# PaxInstrument-T400.net
KiCad netlist of a schematic drawn in EAGLE
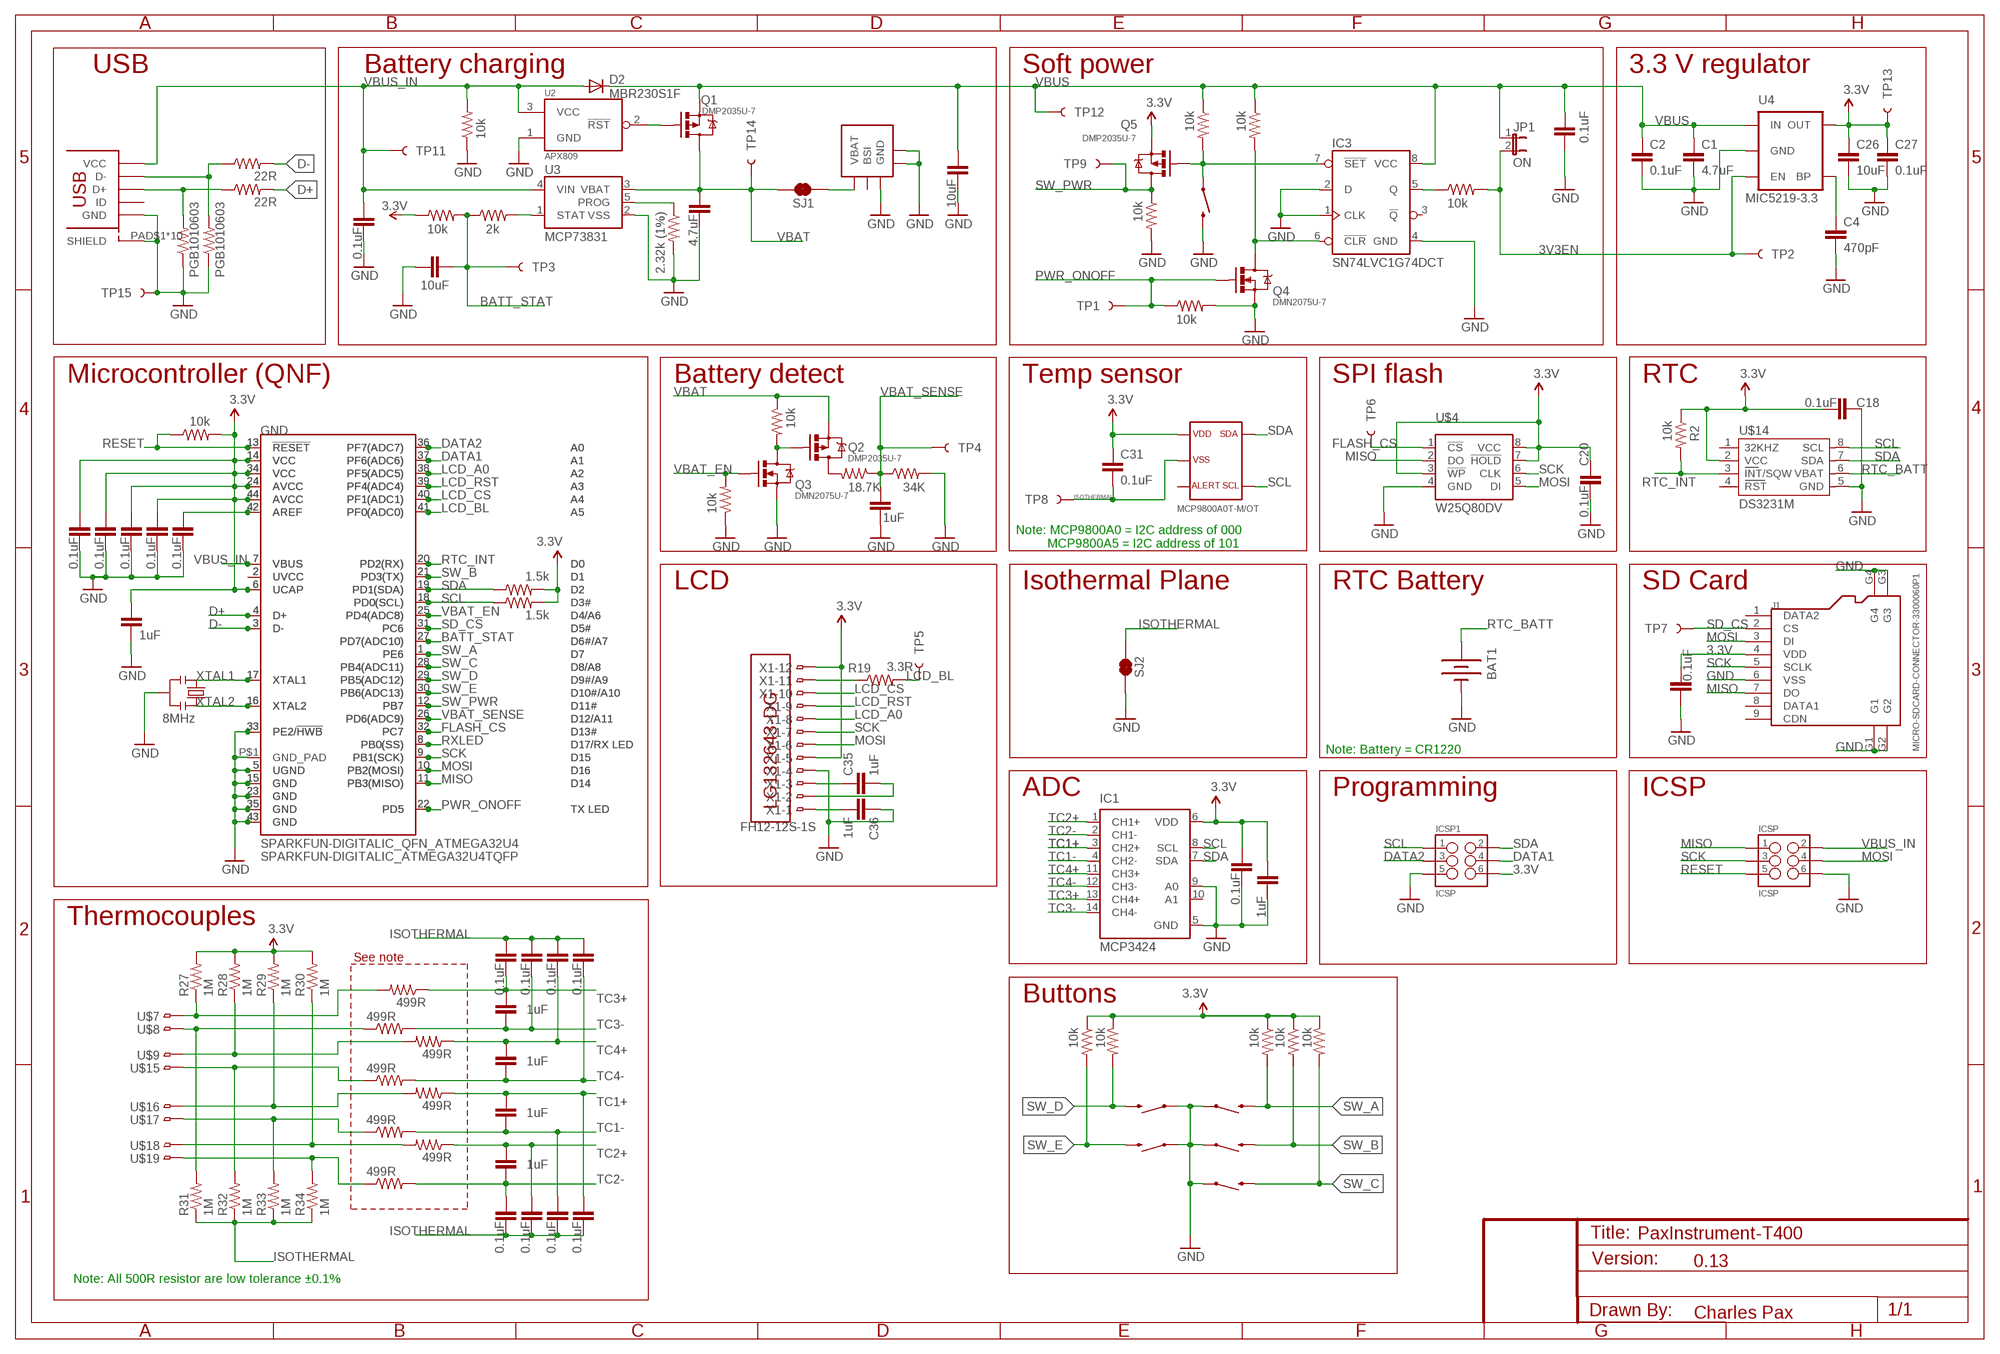
[diagram p0: schematic, sheet 1]

(export (version "E")
  (design (tool "Eeschema 10.0.6"))
  (components
    (comp (ref "BAT1")
      (value "BATTERY12MM")
      (footprint "eagle-import:BATTCON_12MM")
      (fields (field (name "MF") "Keystone Electronics") (field (name "MPN") "3000TR"))
      (libsource (lib "eagle-import") (part "BATTERY12MM"))
    )
    (comp (ref "C1")
      (value "4.7uF")
      (footprint "eagle-import:SPARKFUN-CAPACITORS_0603-CAP")
      (libsource (lib "eagle-import") (part "SPARKFUN-CAPACITORS_CAP0603-CAP"))
    )
    (comp (ref "C2")
      (value "0.1uF")
      (footprint "eagle-import:SPARKFUN-CAPACITORS_0603-CAP")
      (libsource (lib "eagle-import") (part "SPARKFUN-CAPACITORS_CAP0603-CAP"))
    )
    (comp (ref "C3")
      (value "0.1uF")
      (footprint "eagle-import:SPARKFUN-CAPACITORS_0603-CAP")
      (libsource (lib "eagle-import") (part "SPARKFUN-CAPACITORS_CAP0603-CAP"))
    )
    (comp (ref "C4")
      (value "470pF")
      (footprint "eagle-import:SPARKFUN-CAPACITORS_0603-CAP")
      (libsource (lib "eagle-import") (part "SPARKFUN-CAPACITORS_CAP0603-CAP"))
    )
    (comp (ref "C5")
      (value "0.1uF")
      (footprint "eagle-import:SPARKFUN-CAPACITORS_0603-CAP")
      (libsource (lib "eagle-import") (part "SPARKFUN-CAPACITORS_CAP0603-CAP"))
    )
    (comp (ref "C6")
      (value "0.1uF")
      (footprint "eagle-import:SPARKFUN-CAPACITORS_0603-CAP")
      (libsource (lib "eagle-import") (part "SPARKFUN-CAPACITORS_CAP0603-CAP"))
    )
    (comp (ref "C7")
      (value "1uF")
      (footprint "eagle-import:SPARKFUN-CAPACITORS_0603-CAP")
      (libsource (lib "eagle-import") (part "SPARKFUN-CAPACITORS_CAP0603-CAP"))
    )
    (comp (ref "C8")
      (value "1uF")
      (footprint "eagle-import:SPARKFUN-CAPACITORS_0603-CAP")
      (libsource (lib "eagle-import") (part "SPARKFUN-CAPACITORS_CAP0603-CAP"))
    )
    (comp (ref "C9")
      (value "4.7uF")
      (footprint "eagle-import:SPARKFUN-CAPACITORS_0603-CAP")
      (libsource (lib "eagle-import") (part "SPARKFUN-CAPACITORS_CAP0603-CAP"))
    )
    (comp (ref "C10")
      (value "1uF")
      (footprint "eagle-import:SPARKFUN-CAPACITORS_0603-CAP")
      (libsource (lib "eagle-import") (part "SPARKFUN-CAPACITORS_CAP0603-CAP"))
    )
    (comp (ref "C11")
      (value "1uF")
      (footprint "eagle-import:SPARKFUN-CAPACITORS_0603-CAP")
      (libsource (lib "eagle-import") (part "SPARKFUN-CAPACITORS_CAP0603-CAP"))
    )
    (comp (ref "C12")
      (value "10uF")
      (footprint "eagle-import:SPARKFUN-CAPACITORS_0603-CAP")
      (libsource (lib "eagle-import") (part "SPARKFUN-CAPACITORS_CAP0603-CAP"))
    )
    (comp (ref "C13")
      (value "0.1uF")
      (footprint "eagle-import:SPARKFUN-CAPACITORS_0603-CAP")
      (libsource (lib "eagle-import") (part "SPARKFUN-CAPACITORS_CAP0603-CAP"))
    )
    (comp (ref "C14")
      (value "0.1uF")
      (footprint "eagle-import:SPARKFUN-CAPACITORS_0603-CAP")
      (libsource (lib "eagle-import") (part "SPARKFUN-CAPACITORS_CAP0603-CAP"))
    )
    (comp (ref "C15")
      (value "0.1uF")
      (footprint "eagle-import:SPARKFUN-CAPACITORS_0603-CAP")
      (libsource (lib "eagle-import") (part "SPARKFUN-CAPACITORS_CAP0603-CAP"))
    )
    (comp (ref "C16")
      (value "0.1uF")
      (footprint "eagle-import:SPARKFUN-CAPACITORS_0603-CAP")
      (libsource (lib "eagle-import") (part "SPARKFUN-CAPACITORS_CAP0603-CAP"))
    )
    (comp (ref "C17")
      (value "0.1uF")
      (footprint "eagle-import:SPARKFUN-CAPACITORS_0603-CAP")
      (libsource (lib "eagle-import") (part "SPARKFUN-CAPACITORS_CAP0603-CAP"))
    )
    (comp (ref "C18")
      (value "0.1uF")
      (footprint "eagle-import:SPARKFUN-CAPACITORS_0603-CAP")
      (libsource (lib "eagle-import") (part "SPARKFUN-CAPACITORS_CAP0603-CAP"))
    )
    (comp (ref "C19")
      (value "1uF")
      (footprint "eagle-import:SPARKFUN-CAPACITORS_0603-CAP")
      (libsource (lib "eagle-import") (part "SPARKFUN-CAPACITORS_CAP0603-CAP"))
    )
    (comp (ref "C20")
      (value "0.1uF")
      (footprint "eagle-import:SPARKFUN-CAPACITORS_0603-CAP")
      (libsource (lib "eagle-import") (part "SPARKFUN-CAPACITORS_CAP0603-CAP"))
    )
    (comp (ref "C21")
      (value "0.1uF")
      (footprint "eagle-import:SPARKFUN-CAPACITORS_0603-CAP")
      (libsource (lib "eagle-import") (part "SPARKFUN-CAPACITORS_CAP0603-CAP"))
    )
    (comp (ref "C22")
      (value "10uF")
      (footprint "eagle-import:SPARKFUN-CAPACITORS_0603-CAP")
      (libsource (lib "eagle-import") (part "SPARKFUN-CAPACITORS_CAP0603-CAP"))
    )
    (comp (ref "C23")
      (value "1uF")
      (footprint "eagle-import:SPARKFUN-CAPACITORS_0603-CAP")
      (libsource (lib "eagle-import") (part "SPARKFUN-CAPACITORS_CAP0603-CAP"))
    )
    (comp (ref "C24")
      (value "0.1uF")
      (footprint "eagle-import:SPARKFUN-CAPACITORS_0603-CAP")
      (libsource (lib "eagle-import") (part "SPARKFUN-CAPACITORS_CAP0603-CAP"))
    )
    (comp (ref "C25")
      (value "0.1uF")
      (footprint "eagle-import:SPARKFUN-CAPACITORS_0603-CAP")
      (libsource (lib "eagle-import") (part "SPARKFUN-CAPACITORS_CAP0603-CAP"))
    )
    (comp (ref "C26")
      (value "10uF")
      (footprint "eagle-import:SPARKFUN-CAPACITORS_0603-CAP")
      (libsource (lib "eagle-import") (part "SPARKFUN-CAPACITORS_CAP0603-CAP"))
    )
    (comp (ref "C27")
      (value "0.1uF")
      (footprint "eagle-import:SPARKFUN-CAPACITORS_0603-CAP")
      (libsource (lib "eagle-import") (part "SPARKFUN-CAPACITORS_CAP0603-CAP"))
    )
    (comp (ref "C28")
      (value "0.1uF")
      (footprint "eagle-import:SPARKFUN-CAPACITORS_0603-CAP")
      (libsource (lib "eagle-import") (part "SPARKFUN-CAPACITORS_CAP0603-CAP"))
    )
    (comp (ref "C29")
      (value "0.1uF")
      (footprint "eagle-import:SPARKFUN-CAPACITORS_0603-CAP")
      (libsource (lib "eagle-import") (part "SPARKFUN-CAPACITORS_CAP0603-CAP"))
    )
    (comp (ref "C30")
      (value "1uF")
      (footprint "eagle-import:SPARKFUN-CAPACITORS_0603-CAP")
      (libsource (lib "eagle-import") (part "SPARKFUN-CAPACITORS_CAP0603-CAP"))
    )
    (comp (ref "C31")
      (value "0.1uF")
      (footprint "eagle-import:SPARKFUN-CAPACITORS_0603-CAP")
      (libsource (lib "eagle-import") (part "SPARKFUN-CAPACITORS_CAP0603-CAP"))
    )
    (comp (ref "C32")
      (value "0.1uF")
      (footprint "eagle-import:SPARKFUN-CAPACITORS_0603-CAP")
      (libsource (lib "eagle-import") (part "SPARKFUN-CAPACITORS_CAP0603-CAP"))
    )
    (comp (ref "C33")
      (value "0.1uF")
      (footprint "eagle-import:SPARKFUN-CAPACITORS_0603-CAP")
      (libsource (lib "eagle-import") (part "SPARKFUN-CAPACITORS_CAP0603-CAP"))
    )
    (comp (ref "C34")
      (value "0.1uF")
      (footprint "eagle-import:SPARKFUN-CAPACITORS_0603-CAP")
      (libsource (lib "eagle-import") (part "SPARKFUN-CAPACITORS_CAP0603-CAP"))
    )
    (comp (ref "C35")
      (value "1uF")
      (footprint "eagle-import:SPARKFUN-CAPACITORS_0603-CAP")
      (libsource (lib "eagle-import") (part "SPARKFUN-CAPACITORS_CAP0603-CAP"))
    )
    (comp (ref "C36")
      (value "1uF")
      (footprint "eagle-import:SPARKFUN-CAPACITORS_0603-CAP")
      (libsource (lib "eagle-import") (part "SPARKFUN-CAPACITORS_CAP0603-CAP"))
    )
    (comp (ref "C37")
      (value "0.1uF")
      (footprint "eagle-import:SPARKFUN-CAPACITORS_0603-CAP")
      (libsource (lib "eagle-import") (part "SPARKFUN-CAPACITORS_CAP0603-CAP"))
    )
    (comp (ref "D2")
      (value "MBR230S1F")
      (footprint "eagle-import:SOD123")
      (fields (field (name "MF") "DIODES INC") (field (name "MPN") "MBR230S1F-7"))
      (libsource (lib "eagle-import") (part "SPARKFUN-DISCRETESEMI_DIODESOD123SOD123"))
    )
    (comp (ref "GND")
      (value "SPARKFUN-DIGITALIC_QFN_ATMEGA32U4")
      (footprint "eagle-import:SPARKFUN-DIGITALIC_SPARKFUN-DIGITALIC_QFN-44")
      (fields (field (name "MF") "Atmel") (field (name "MPN") "ATMEGA32U4-MU"))
      (libsource (lib "eagle-import") (part "SPARKFUN-DIGITALIC_QFN_ATMEGA32U4"))
    )
    (comp (ref "IC1")
      (value "MCP3424")
      (footprint "eagle-import:SO14")
      (fields (field (name "MF") "Microchip Technology") (field (name "MPN") "MCP3424-E/SL"))
      (libsource (lib "eagle-import") (part "MCP3424"))
    )
    (comp (ref "IC3")
      (value "SN74LVC1G74DCT")
      (footprint "eagle-import:SSOP8")
      (fields (field (name "MF") "Texas Instruments") (field (name "MPN") "SN74LVC1G74DCTR "))
      (libsource (lib "eagle-import") (part "SN74LVC1G74DCT"))
    )
    (comp (ref "ICSP")
      (value "ICSP")
      (footprint "eagle-import:SPARKFUN-CONNECTORS_2X3_SMT_POSTS_PAXINSTRUMENT")
      (fields (field (name "MF") "FCI") (field (name "MPN") "95278-101A06LF"))
      (libsource (lib "eagle-import") (part "SPARKFUN-CONNECTORS_M03X2PAX"))
    )
    (comp (ref "ICSP1")
      (value "ICSP")
      (footprint "eagle-import:SPARKFUN-CONNECTORS_2X3_SMT_POSTS_PAXINSTRUMENT")
      (fields (field (name "MF") "FCI") (field (name "MPN") "95278-101A06LF"))
      (libsource (lib "eagle-import") (part "SPARKFUN-CONNECTORS_M03X2PAX"))
    )
    (comp (ref "J1")
      (value "MICRO-SDCARD-CONNECTOR-3300060P1")
      (footprint "eagle-import:9P-SMD-W-RING")
      (fields (field (name "MF") "SUNTECH") (field (name "MPN") "ST-TF-003A"))
      (libsource (lib "eagle-import") (part "MICRO-SDCARD-CONNECTOR-3300060P1"))
    )
    (comp (ref "JP1")
      (value "ON")
      (footprint "eagle-import:SJ_2S-NO")
      (libsource (lib "eagle-import") (part "JUMPER-2SMD-NO"))
    )
    (comp (ref "Q1")
      (value "DMP2035U-7")
      (footprint "eagle-import:SOT23")
      (fields (field (name "MF") "DIODES INC"))
      (libsource (lib "eagle-import") (part "MOSFET-PCHANNELSMT"))
    )
    (comp (ref "Q2")
      (value "DMP2035U-7")
      (footprint "eagle-import:SOT23")
      (fields (field (name "MF") "DIODES INC"))
      (libsource (lib "eagle-import") (part "MOSFET-PCHANNELSMT"))
    )
    (comp (ref "Q3")
      (value "DMN2075U-7")
      (footprint "eagle-import:SOT23")
      (fields (field (name "MF") "DIODES INC") (field (name "MPN") "DMN2075U-7 "))
      (libsource (lib "eagle-import") (part "MOSFET-NCHANNELSMT"))
    )
    (comp (ref "Q4")
      (value "DMN2075U-7")
      (footprint "eagle-import:SOT23")
      (fields (field (name "MF") "DIODES INC") (field (name "MPN") "DMN2075U-7 "))
      (libsource (lib "eagle-import") (part "MOSFET-NCHANNELSMT"))
    )
    (comp (ref "Q5")
      (value "DMP2035U-7")
      (footprint "eagle-import:SOT23")
      (fields (field (name "MF") "DIODES INC"))
      (libsource (lib "eagle-import") (part "MOSFET-PCHANNELSMT"))
    )
    (comp (ref "R1")
      (value "10k")
      (footprint "eagle-import:SPARKFUN-RESISTORS_0603-RES")
      (libsource (lib "eagle-import") (part "SPARKFUN-RESISTORS_RESISTOR0603-RES"))
    )
    (comp (ref "R2")
      (value "10k")
      (footprint "eagle-import:SPARKFUN-RESISTORS_0603-RES")
      (libsource (lib "eagle-import") (part "SPARKFUN-RESISTORS_RESISTOR0603-RES"))
    )
    (comp (ref "R3")
      (value "2.32k (1%)")
      (footprint "eagle-import:SPARKFUN-RESISTORS_0603-RES")
      (libsource (lib "eagle-import") (part "SPARKFUN-RESISTORS_RESISTOR0603-RES"))
    )
    (comp (ref "R4")
      (value "10k")
      (footprint "eagle-import:SPARKFUN-RESISTORS_0603-RES")
      (libsource (lib "eagle-import") (part "SPARKFUN-RESISTORS_RESISTOR0603-RES"))
    )
    (comp (ref "R5")
      (value "10k")
      (footprint "eagle-import:SPARKFUN-RESISTORS_0603-RES")
      (libsource (lib "eagle-import") (part "SPARKFUN-RESISTORS_RESISTOR0603-RES"))
    )
    (comp (ref "R6")
      (value "10k")
      (footprint "eagle-import:SPARKFUN-RESISTORS_0603-RES")
      (libsource (lib "eagle-import") (part "SPARKFUN-RESISTORS_RESISTOR0603-RES"))
    )
    (comp (ref "R7")
      (value "10k")
      (footprint "eagle-import:SPARKFUN-RESISTORS_0603-RES")
      (libsource (lib "eagle-import") (part "SPARKFUN-RESISTORS_RESISTOR0603-RES"))
    )
    (comp (ref "R8")
      (value "10k")
      (footprint "eagle-import:SPARKFUN-RESISTORS_0603-RES")
      (libsource (lib "eagle-import") (part "SPARKFUN-RESISTORS_RESISTOR0603-RES"))
    )
    (comp (ref "R9")
      (value "22R")
      (footprint "eagle-import:SPARKFUN-RESISTORS_0603-RES")
      (libsource (lib "eagle-import") (part "SPARKFUN-RESISTORS_RESISTOR0603-RES"))
    )
    (comp (ref "R10")
      (value "22R")
      (footprint "eagle-import:SPARKFUN-RESISTORS_0603-RES")
      (libsource (lib "eagle-import") (part "SPARKFUN-RESISTORS_RESISTOR0603-RES"))
    )
    (comp (ref "R11")
      (value "10k")
      (footprint "eagle-import:SPARKFUN-RESISTORS_0603-RES")
      (libsource (lib "eagle-import") (part "SPARKFUN-RESISTORS_RESISTOR0603-RES"))
    )
    (comp (ref "R12")
      (value "10k")
      (footprint "eagle-import:SPARKFUN-RESISTORS_0603-RES")
      (libsource (lib "eagle-import") (part "SPARKFUN-RESISTORS_RESISTOR0603-RES"))
    )
    (comp (ref "R13")
      (value "1.5k")
      (footprint "eagle-import:SPARKFUN-RESISTORS_0603-RES")
      (libsource (lib "eagle-import") (part "SPARKFUN-RESISTORS_RESISTOR0603-RES"))
    )
    (comp (ref "R14")
      (value "1.5k")
      (footprint "eagle-import:SPARKFUN-RESISTORS_0603-RES")
      (libsource (lib "eagle-import") (part "SPARKFUN-RESISTORS_RESISTOR0603-RES"))
    )
    (comp (ref "R15")
      (value "10k")
      (footprint "eagle-import:SPARKFUN-RESISTORS_0603-RES")
      (libsource (lib "eagle-import") (part "SPARKFUN-RESISTORS_RESISTOR0603-RES"))
    )
    (comp (ref "R16")
      (value "10k")
      (footprint "eagle-import:SPARKFUN-RESISTORS_0603-RES")
      (libsource (lib "eagle-import") (part "SPARKFUN-RESISTORS_RESISTOR0603-RES"))
    )
    (comp (ref "R17")
      (value "2k")
      (footprint "eagle-import:SPARKFUN-RESISTORS_0603-RES")
      (libsource (lib "eagle-import") (part "SPARKFUN-RESISTORS_RESISTOR0603-RES"))
    )
    (comp (ref "R18")
      (value "10k")
      (footprint "eagle-import:SPARKFUN-RESISTORS_0603-RES")
      (libsource (lib "eagle-import") (part "SPARKFUN-RESISTORS_RESISTOR0603-RES"))
    )
    (comp (ref "R19")
      (value "3.3R")
      (footprint "eagle-import:SPARKFUN-RESISTORS_0603-RES")
      (libsource (lib "eagle-import") (part "SPARKFUN-RESISTORS_RESISTOR0603-RES"))
    )
    (comp (ref "R20")
      (value "18.7K")
      (footprint "eagle-import:SPARKFUN-RESISTORS_0603-RES")
      (libsource (lib "eagle-import") (part "SPARKFUN-RESISTORS_RESISTOR0603-RES"))
    )
    (comp (ref "R21")
      (value "10k")
      (footprint "eagle-import:SPARKFUN-RESISTORS_0603-RES")
      (libsource (lib "eagle-import") (part "SPARKFUN-RESISTORS_RESISTOR0603-RES"))
    )
    (comp (ref "R22")
      (value "10k")
      (footprint "eagle-import:SPARKFUN-RESISTORS_0603-RES")
      (libsource (lib "eagle-import") (part "SPARKFUN-RESISTORS_RESISTOR0603-RES"))
    )
    (comp (ref "R23")
      (value "10k")
      (footprint "eagle-import:SPARKFUN-RESISTORS_0603-RES")
      (libsource (lib "eagle-import") (part "SPARKFUN-RESISTORS_RESISTOR0603-RES"))
    )
    (comp (ref "R24")
      (value "34K")
      (footprint "eagle-import:SPARKFUN-RESISTORS_0603-RES")
      (libsource (lib "eagle-import") (part "SPARKFUN-RESISTORS_RESISTOR0603-RES"))
    )
    (comp (ref "R25")
      (value "10k")
      (footprint "eagle-import:SPARKFUN-RESISTORS_0603-RES")
      (libsource (lib "eagle-import") (part "SPARKFUN-RESISTORS_RESISTOR0603-RES"))
    )
    (comp (ref "R27")
      (value "1M")
      (footprint "eagle-import:SPARKFUN-RESISTORS_0603-RES")
      (libsource (lib "eagle-import") (part "SPARKFUN-RESISTORS_RESISTOR0603-RES"))
    )
    (comp (ref "R28")
      (value "1M")
      (footprint "eagle-import:SPARKFUN-RESISTORS_0603-RES")
      (libsource (lib "eagle-import") (part "SPARKFUN-RESISTORS_RESISTOR0603-RES"))
    )
    (comp (ref "R29")
      (value "1M")
      (footprint "eagle-import:SPARKFUN-RESISTORS_0603-RES")
      (libsource (lib "eagle-import") (part "SPARKFUN-RESISTORS_RESISTOR0603-RES"))
    )
    (comp (ref "R30")
      (value "1M")
      (footprint "eagle-import:SPARKFUN-RESISTORS_0603-RES")
      (libsource (lib "eagle-import") (part "SPARKFUN-RESISTORS_RESISTOR0603-RES"))
    )
    (comp (ref "R31")
      (value "1M")
      (footprint "eagle-import:SPARKFUN-RESISTORS_0603-RES")
      (libsource (lib "eagle-import") (part "SPARKFUN-RESISTORS_RESISTOR0603-RES"))
    )
    (comp (ref "R32")
      (value "1M")
      (footprint "eagle-import:SPARKFUN-RESISTORS_0603-RES")
      (libsource (lib "eagle-import") (part "SPARKFUN-RESISTORS_RESISTOR0603-RES"))
    )
    (comp (ref "R33")
      (value "1M")
      (footprint "eagle-import:SPARKFUN-RESISTORS_0603-RES")
      (libsource (lib "eagle-import") (part "SPARKFUN-RESISTORS_RESISTOR0603-RES"))
    )
    (comp (ref "R34")
      (value "1M")
      (footprint "eagle-import:SPARKFUN-RESISTORS_0603-RES")
      (libsource (lib "eagle-import") (part "SPARKFUN-RESISTORS_RESISTOR0603-RES"))
    )
    (comp (ref "R35")
      (value "499R")
      (footprint "eagle-import:SPARKFUN-RESISTORS_0603-RES")
      (fields (field (name "MF") "Vishay") (field (name "MPN") "TNPW0603499RBEEA"))
      (libsource (lib "eagle-import") (part "SPARKFUN-RESISTORS_RESISTOR0603-RES"))
    )
    (comp (ref "R36")
      (value "499R")
      (footprint "eagle-import:SPARKFUN-RESISTORS_0603-RES")
      (fields (field (name "MF") "Vishay") (field (name "MPN") "TNPW0603499RBEEA"))
      (libsource (lib "eagle-import") (part "SPARKFUN-RESISTORS_RESISTOR0603-RES"))
    )
    (comp (ref "R37")
      (value "499R")
      (footprint "eagle-import:SPARKFUN-RESISTORS_0603-RES")
      (fields (field (name "MF") "Vishay") (field (name "MPN") "TNPW0603499RBEEA"))
      (libsource (lib "eagle-import") (part "SPARKFUN-RESISTORS_RESISTOR0603-RES"))
    )
    (comp (ref "R38")
      (value "499R")
      (footprint "eagle-import:SPARKFUN-RESISTORS_0603-RES")
      (fields (field (name "MF") "Vishay") (field (name "MPN") "TNPW0603499RBEEA"))
      (libsource (lib "eagle-import") (part "SPARKFUN-RESISTORS_RESISTOR0603-RES"))
    )
    (comp (ref "R39")
      (value "499R")
      (footprint "eagle-import:SPARKFUN-RESISTORS_0603-RES")
      (fields (field (name "MF") "Vishay") (field (name "MPN") "TNPW0603499RBEEA"))
      (libsource (lib "eagle-import") (part "SPARKFUN-RESISTORS_RESISTOR0603-RES"))
    )
    (comp (ref "R40")
      (value "499R")
      (footprint "eagle-import:SPARKFUN-RESISTORS_0603-RES")
      (fields (field (name "MF") "Vishay") (field (name "MPN") "TNPW0603499RBEEA"))
      (libsource (lib "eagle-import") (part "SPARKFUN-RESISTORS_RESISTOR0603-RES"))
    )
    (comp (ref "R41")
      (value "499R")
      (footprint "eagle-import:SPARKFUN-RESISTORS_0603-RES")
      (fields (field (name "MF") "Vishay") (field (name "MPN") "TNPW0603499RBEEA"))
      (libsource (lib "eagle-import") (part "SPARKFUN-RESISTORS_RESISTOR0603-RES"))
    )
    (comp (ref "R42")
      (value "499R")
      (footprint "eagle-import:SPARKFUN-RESISTORS_0603-RES")
      (fields (field (name "MF") "Vishay") (field (name "MPN") "TNPW0603499RBEEA"))
      (libsource (lib "eagle-import") (part "SPARKFUN-RESISTORS_RESISTOR0603-RES"))
    )
    (comp (ref "S1")
      (value "SWITCH-MOMENTARY-2SMD")
      (footprint "eagle-import:TACTILE_SWITCH_SMD")
      (fields (field (name "MF") "C&K Components") (field (name "MPN") "RS-187R05A2-DS MT RT"))
      (libsource (lib "eagle-import") (part "SWITCH-MOMENTARY-2SMD"))
    )
    (comp (ref "S2")
      (value "SWITCH-MOMENTARY-2SMD")
      (footprint "eagle-import:TACTILE_SWITCH_SMD")
      (fields (field (name "MF") "C&K Components") (field (name "MPN") "RS-187R05A2-DS MT RT"))
      (libsource (lib "eagle-import") (part "SWITCH-MOMENTARY-2SMD"))
    )
    (comp (ref "S3")
      (value "SWITCH-MOMENTARY-2SMD")
      (footprint "eagle-import:TACTILE_SWITCH_SMD")
      (fields (field (name "MF") "C&K Components") (field (name "MPN") "RS-187R05A2-DS MT RT"))
      (libsource (lib "eagle-import") (part "SWITCH-MOMENTARY-2SMD"))
    )
    (comp (ref "S4")
      (value "SWITCH-MOMENTARY-2SMD")
      (footprint "eagle-import:TACTILE_SWITCH_SMD")
      (fields (field (name "MF") "C&K Components") (field (name "MPN") "RS-187R05A2-DS MT RT"))
      (libsource (lib "eagle-import") (part "SWITCH-MOMENTARY-2SMD"))
    )
    (comp (ref "S5")
      (value "SWITCH-MOMENTARY-2SMD")
      (footprint "eagle-import:TACTILE_SWITCH_SMD")
      (fields (field (name "MF") "C&K Components") (field (name "MPN") "RS-187R05A2-DS MT RT"))
      (libsource (lib "eagle-import") (part "SWITCH-MOMENTARY-2SMD"))
    )
    (comp (ref "S6")
      (value "SWITCH-MOMENTARY-2SMD")
      (footprint "eagle-import:TACTILE_SWITCH_SMD")
      (fields (field (name "MF") "C&K Components") (field (name "MPN") "RS-187R05A2-DS MT RT"))
      (libsource (lib "eagle-import") (part "SWITCH-MOMENTARY-2SMD"))
    )
    (comp (ref "SJ1")
      (value "JUMPER-PAD-2-NC_BY_TRACE")
      (footprint "eagle-import:PAD-JUMPER-2-NC_BY_TRACE_YES_SILK")
      (libsource (lib "eagle-import") (part "JUMPER-PAD-2-NC_BY_TRACE"))
    )
    (comp (ref "SJ2")
      (value "JUMPER-PAD-2-NC_BY_TRACE")
      (footprint "eagle-import:PAD-JUMPER-2-NC_BY_TRACE_YES_SILK")
      (libsource (lib "eagle-import") (part "JUMPER-PAD-2-NC_BY_TRACE"))
    )
    (comp (ref "TP1")
      (value "PWR_ONOFF")
      (footprint "eagle-import:TP_15TH")
      (libsource (lib "eagle-import") (part "TEST-POINTTP_15TH_THRU"))
    )
    (comp (ref "TP2")
      (value "3V3_EN")
      (footprint "eagle-import:TP_15TH")
      (libsource (lib "eagle-import") (part "TEST-POINTTP_15TH_THRU"))
    )
    (comp (ref "TP3")
      (value "BATT_STAT")
      (footprint "eagle-import:TP_15TH")
      (libsource (lib "eagle-import") (part "TEST-POINTTP_15TH_THRU"))
    )
    (comp (ref "TP4")
      (value "VBAT_SENSE")
      (footprint "eagle-import:TP_15TH")
      (libsource (lib "eagle-import") (part "TEST-POINTTP_15TH_THRU"))
    )
    (comp (ref "TP5")
      (value "LCD_BL")
      (footprint "eagle-import:TP_15TH")
      (libsource (lib "eagle-import") (part "TEST-POINTTP_15TH_THRU"))
    )
    (comp (ref "TP6")
      (value "FLASH_CS")
      (footprint "eagle-import:TP_15TH")
      (libsource (lib "eagle-import") (part "TEST-POINTTP_15TH_THRU"))
    )
    (comp (ref "TP7")
      (value "SD_CS")
      (footprint "eagle-import:TP_15TH")
      (libsource (lib "eagle-import") (part "TEST-POINTTP_15TH_THRU"))
    )
    (comp (ref "TP8")
      (value "ISOTHERMAL")
      (footprint "eagle-import:TP_15TH")
      (libsource (lib "eagle-import") (part "TEST-POINTTP_15TH_THRU"))
    )
    (comp (ref "TP9")
      (value "SW_PWR")
      (footprint "eagle-import:TP_15TH")
      (libsource (lib "eagle-import") (part "TEST-POINTTP_15TH_THRU"))
    )
    (comp (ref "TP11")
      (value "VBUS_IN")
      (footprint "eagle-import:TP_15TH")
      (libsource (lib "eagle-import") (part "TEST-POINTTP_15TH_THRU"))
    )
    (comp (ref "TP12")
      (value "VBUS")
      (footprint "eagle-import:TP_15TH")
      (libsource (lib "eagle-import") (part "TEST-POINTTP_15TH_THRU"))
    )
    (comp (ref "TP13")
      (value "3.3V")
      (footprint "eagle-import:TP_15TH")
      (libsource (lib "eagle-import") (part "TEST-POINTTP_15TH_THRU"))
    )
    (comp (ref "TP14")
      (value "VBAT")
      (footprint "eagle-import:TP_15TH")
      (libsource (lib "eagle-import") (part "TEST-POINTTP_15TH_THRU"))
    )
    (comp (ref "TP15")
      (value "GND")
      (footprint "eagle-import:TP_15TH")
      (libsource (lib "eagle-import") (part "TEST-POINTTP_15TH_THRU"))
    )
    (comp (ref "U$1")
      (value "USB_MICROSMT+THRUHULE")
      (footprint "eagle-import:USB_MICRO_THRUHOLE")
      (fields (field (name "MF") "FCI") (field (name "MPN") "10118194-0001LF"))
      (libsource (lib "eagle-import") (part "USB_MICROSMT+THRUHULE"))
    )
    (comp (ref "U$2")
      (value "BL-5C-CONNECTOR")
      (footprint "eagle-import:BL-5C-CONNECTOR")
      (fields (field (name "MPN") "BC-4-3P (77H)"))
      (libsource (lib "eagle-import") (part "BL-5C-CONNECTOR"))
    )
    (comp (ref "U$3")
      (value "SPARKFUN-DIGITALIC_ATMEGA32U4TQFP")
      (footprint "eagle-import:SPARKFUN-DIGITALIC_SPARKFUN-DIGITALIC_TQFP44")
      (fields (field (name "MF") "Atmel") (field (name "MPN") "ATMEGA32U4-AU"))
      (libsource (lib "eagle-import") (part "SPARKFUN-DIGITALIC_ATMEGA32U4TQFP"))
    )
    (comp (ref "U$4")
      (value "W25Q80DV")
      (footprint "eagle-import:CHARLESPAX_SOIC8M")
      (fields (field (name "MF") "Winbond Electronics") (field (name "MPN") "W25Q80DVSSIG-ND"))
      (libsource (lib "eagle-import") (part "W25Q80BV"))
    )
    (comp (ref "U$5")
      (value "LG132643-DG")
      (footprint "eagle-import:LG132643-DG")
      (fields (field (name "MPN") "LG132643-DW"))
      (libsource (lib "eagle-import") (part "LG132643-DG"))
    )
    (comp (ref "U$7")
      (value "TC-MINI-SINGLE")
      (footprint "eagle-import:TC-CLIP-SINGLE")
      (fields (field (name "MF") "Pax Instrument") (field (name "MPN") "Thermo-clip2"))
      (libsource (lib "eagle-import") (part "TC-MINI-SINGLE"))
    )
    (comp (ref "U$8")
      (value "TC-MINI-SINGLE")
      (footprint "eagle-import:TC-CLIP-SINGLE")
      (fields (field (name "MF") "Pax Instrument") (field (name "MPN") "Thermo-clip2"))
      (libsource (lib "eagle-import") (part "TC-MINI-SINGLE"))
    )
    (comp (ref "U$9")
      (value "TC-MINI-SINGLE")
      (footprint "eagle-import:TC-CLIP-SINGLE")
      (fields (field (name "MF") "Pax Instrument") (field (name "MPN") "Thermo-clip2"))
      (libsource (lib "eagle-import") (part "TC-MINI-SINGLE"))
    )
    (comp (ref "U$14")
      (value "DS3231M")
      (footprint "eagle-import:SOIC8")
      (fields (field (name "MF") "Maxim Integrated") (field (name "MPN") "DS3231MZ+"))
      (libsource (lib "eagle-import") (part "DS3231M"))
    )
    (comp (ref "U$15")
      (value "TC-MINI-SINGLE")
      (footprint "eagle-import:TC-CLIP-SINGLE")
      (fields (field (name "MF") "Pax Instrument") (field (name "MPN") "Thermo-clip2"))
      (libsource (lib "eagle-import") (part "TC-MINI-SINGLE"))
    )
    (comp (ref "U$16")
      (value "TC-MINI-SINGLE")
      (footprint "eagle-import:TC-CLIP-SINGLE")
      (fields (field (name "MF") "Pax Instrument") (field (name "MPN") "Thermo-clip2"))
      (libsource (lib "eagle-import") (part "TC-MINI-SINGLE"))
    )
    (comp (ref "U$17")
      (value "TC-MINI-SINGLE")
      (footprint "eagle-import:TC-CLIP-SINGLE")
      (fields (field (name "MF") "Pax Instrument") (field (name "MPN") "Thermo-clip2"))
      (libsource (lib "eagle-import") (part "TC-MINI-SINGLE"))
    )
    (comp (ref "U$18")
      (value "TC-MINI-SINGLE")
      (footprint "eagle-import:TC-CLIP-SINGLE")
      (fields (field (name "MF") "Pax Instrument") (field (name "MPN") "Thermo-clip2"))
      (libsource (lib "eagle-import") (part "TC-MINI-SINGLE"))
    )
    (comp (ref "U$19")
      (value "TC-MINI-SINGLE")
      (footprint "eagle-import:TC-CLIP-SINGLE")
      (fields (field (name "MF") "Pax Instrument") (field (name "MPN") "Thermo-clip2"))
      (libsource (lib "eagle-import") (part "TC-MINI-SINGLE"))
    )
    (comp (ref "U1")
      (value "MCP9800")
      (footprint "eagle-import:SOT23-5L")
      (fields (field (name "MF") "Microchip Technology") (field (name "MPN") "MCP9800A0T-M/OT"))
      (libsource (lib "eagle-import") (part "MCP9800"))
    )
    (comp (ref "U2")
      (value "APX809")
      (footprint "eagle-import:SOT23")
      (fields (field (name "MF") "DIODES INC") (field (name "MPN") "APX809-44SAG-7"))
      (libsource (lib "eagle-import") (part "APX809"))
    )
    (comp (ref "U3")
      (value "MCP73831")
      (footprint "eagle-import:SOT23-5")
      (fields (field (name "MF") "Microchip Technology") (field (name "MPN") "MCP73832T-2DCI/OT"))
      (libsource (lib "eagle-import") (part "MCP73831"))
    )
    (comp (ref "U4")
      (value "MIC5219-3.3V")
      (footprint "eagle-import:SOT23-5")
      (fields (field (name "MF") "Micrel") (field (name "MPN") "MIC5219-3.3YM5 TR"))
      (libsource (lib "eagle-import") (part "V_REG_LDOSMD"))
    )
    (comp (ref "X1")
      (value "FH12-12S-1S")
      (footprint "eagle-import:FH12-12S-1SH")
      (fields (field (name "MF") "Hirose Connector") (field (name "MPN") "FH12-12S-1SH(55)"))
      (libsource (lib "eagle-import") (part "FH12-12S-1S"))
    )
    (comp (ref "Y1")
      (value "RESONATORSMD")
      (footprint "eagle-import:RESONATOR-SMD")
      (fields (field (name "MF") "Murata Electronics") (field (name "MPN") "CSTCE8M00G52-R0"))
      (libsource (lib "eagle-import") (part "RESONATORSMD"))
    )
    (comp (ref "Z1")
      (value "PGB1010603")
      (footprint "eagle-import:SPARKFUN-RESISTORS_0603-RES")
      (fields (field (name "MF") "Littelfuse") (field (name "MPN") "PGB1010603NRHF"))
      (libsource (lib "eagle-import") (part "SPARKFUN-RESISTORS_RESISTOR0603-RES"))
    )
    (comp (ref "Z2")
      (value "PGB1010603")
      (footprint "eagle-import:SPARKFUN-RESISTORS_0603-RES")
      (fields (field (name "MF") "Littelfuse") (field (name "MPN") "PGB1010603NRHF"))
      (libsource (lib "eagle-import") (part "SPARKFUN-RESISTORS_RESISTOR0603-RES"))
    )
  )
  (nets
    (net (code "1") (name "/3V3EN") (class "Default")
      (node (ref "JP1") (pin "2") (pinfunction "2_2") (pintype "passive"))
      (node (ref "R21") (pin "2") (pinfunction "2_2") (pintype "passive"))
      (node (ref "TP2") (pin "P$1") (pinfunction "1_P$1") (pintype "bidirectional"))
      (node (ref "U4") (pin "3") (pinfunction "EN_3") (pintype "input"))
    )
    (net (code "2") (name "/BATT_STAT") (class "Default")
      (node (ref "C22") (pin "1") (pinfunction "1_1") (pintype "passive"))
      (node (ref "GND") (pin "27") (pinfunction "PD7(ADC10)_27") (pintype "bidirectional"))
      (node (ref "R1") (pin "2") (pinfunction "2_2") (pintype "passive"))
      (node (ref "R17") (pin "1") (pinfunction "1_1") (pintype "passive"))
      (node (ref "TP3") (pin "P$1") (pinfunction "1_P$1") (pintype "bidirectional"))
      (node (ref "U$3") (pin "27") (pinfunction "PD7(ADC10)_27") (pintype "bidirectional"))
    )
    (net (code "3") (name "/DATA1") (class "Default")
      (node (ref "GND") (pin "37") (pinfunction "PF6(ADC6)_37") (pintype "bidirectional"))
      (node (ref "ICSP1") (pin "4") (pinfunction "4_4") (pintype "bidirectional"))
      (node (ref "U$3") (pin "37") (pinfunction "PF6(ADC6)_37") (pintype "bidirectional"))
    )
    (net (code "4") (name "/DATA2") (class "Default")
      (node (ref "GND") (pin "36") (pinfunction "PF7(ADC7)_36") (pintype "bidirectional"))
      (node (ref "ICSP1") (pin "3") (pinfunction "3_3") (pintype "bidirectional"))
      (node (ref "U$3") (pin "36") (pinfunction "PF7(ADC7)_36") (pintype "bidirectional"))
    )
    (net (code "5") (name "/FLASH_CS") (class "Default")
      (node (ref "GND") (pin "32") (pinfunction "PC7_32") (pintype "bidirectional"))
      (node (ref "TP6") (pin "P$1") (pinfunction "1_P$1") (pintype "bidirectional"))
      (node (ref "U$3") (pin "32") (pinfunction "PC7_32") (pintype "bidirectional"))
      (node (ref "U$4") (pin "1") (pinfunction "~{CS}_1") (pintype "bidirectional"))
    )
    (net (code "6") (name "/ISOTHERMAL") (class "Default")
      (node (ref "C13") (pin "2") (pinfunction "2_2") (pintype "passive"))
      (node (ref "C14") (pin "2") (pinfunction "2_2") (pintype "passive"))
      (node (ref "C15") (pin "2") (pinfunction "2_2") (pintype "passive"))
      (node (ref "C16") (pin "2") (pinfunction "2_2") (pintype "passive"))
      (node (ref "C17") (pin "1") (pinfunction "1_1") (pintype "passive"))
      (node (ref "C24") (pin "1") (pinfunction "1_1") (pintype "passive"))
      (node (ref "C25") (pin "1") (pinfunction "1_1") (pintype "passive"))
      (node (ref "C31") (pin "2") (pinfunction "2_2") (pintype "passive"))
      (node (ref "C37") (pin "1") (pinfunction "1_1") (pintype "passive"))
      (node (ref "R31") (pin "1") (pinfunction "1_1") (pintype "passive"))
      (node (ref "R32") (pin "1") (pinfunction "1_1") (pintype "passive"))
      (node (ref "R33") (pin "1") (pinfunction "1_1") (pintype "passive"))
      (node (ref "R34") (pin "1") (pinfunction "1_1") (pintype "passive"))
      (node (ref "SJ2") (pin "2") (pinfunction "2_2") (pintype "passive"))
      (node (ref "TP8") (pin "P$1") (pinfunction "1_P$1") (pintype "bidirectional"))
      (node (ref "U1") (pin "2") (pinfunction "2_2") (pintype "bidirectional"))
    )
    (net (code "7") (name "/LCD_A0") (class "Default")
      (node (ref "GND") (pin "38") (pinfunction "PF5(ADC5)_38") (pintype "bidirectional"))
      (node (ref "U$3") (pin "38") (pinfunction "PF5(ADC5)_38") (pintype "bidirectional"))
      (node (ref "X1") (pin "8") (pinfunction "1_8") (pintype "passive"))
    )
    (net (code "8") (name "/LCD_BL") (class "Default")
      (node (ref "GND") (pin "41") (pinfunction "PF0(ADC0)_41") (pintype "bidirectional"))
      (node (ref "R19") (pin "2") (pinfunction "2_2") (pintype "passive"))
      (node (ref "TP5") (pin "P$1") (pinfunction "1_P$1") (pintype "bidirectional"))
      (node (ref "U$3") (pin "41") (pinfunction "PF0(ADC0)_41") (pintype "bidirectional"))
    )
    (net (code "9") (name "/LCD_CS") (class "Default")
      (node (ref "GND") (pin "40") (pinfunction "PF1(ADC1)_40") (pintype "bidirectional"))
      (node (ref "U$3") (pin "40") (pinfunction "PF1(ADC1)_40") (pintype "bidirectional"))
      (node (ref "X1") (pin "10") (pinfunction "1_10") (pintype "passive"))
    )
    (net (code "10") (name "/LCD_RST") (class "Default")
      (node (ref "GND") (pin "39") (pinfunction "PF4(ADC4)_39") (pintype "bidirectional"))
      (node (ref "U$3") (pin "39") (pinfunction "PF4(ADC4)_39") (pintype "bidirectional"))
      (node (ref "X1") (pin "9") (pinfunction "1_9") (pintype "passive"))
    )
    (net (code "11") (name "/MISO") (class "Default")
      (node (ref "GND") (pin "11") (pinfunction "PB3(MISO)_11") (pintype "bidirectional"))
      (node (ref "ICSP") (pin "1") (pinfunction "1_1") (pintype "bidirectional"))
      (node (ref "J1") (pin "7") (pinfunction "DO_7") (pintype "bidirectional"))
      (node (ref "U$3") (pin "11") (pinfunction "PB3(MISO)_11") (pintype "bidirectional"))
      (node (ref "U$4") (pin "2") (pinfunction "DO_2") (pintype "bidirectional"))
    )
    (net (code "12") (name "/MOSI") (class "Default")
      (node (ref "GND") (pin "10") (pinfunction "PB2(MOSI)_10") (pintype "bidirectional"))
      (node (ref "ICSP") (pin "4") (pinfunction "4_4") (pintype "bidirectional"))
      (node (ref "J1") (pin "3") (pinfunction "DI_3") (pintype "bidirectional"))
      (node (ref "U$3") (pin "10") (pinfunction "PB2(MOSI)_10") (pintype "bidirectional"))
      (node (ref "U$4") (pin "5") (pinfunction "DI_5") (pintype "bidirectional"))
      (node (ref "X1") (pin "6") (pinfunction "1_6") (pintype "passive"))
    )
    (net (code "13") (name "/PWR_ONOFF") (class "Default")
      (node (ref "GND") (pin "22") (pinfunction "PD5_22") (pintype "bidirectional"))
      (node (ref "Q4") (pin "1") (pinfunction "G_1") (pintype "passive"))
      (node (ref "R22") (pin "1") (pinfunction "1_1") (pintype "passive"))
      (node (ref "TP1") (pin "P$1") (pinfunction "1_P$1") (pintype "bidirectional"))
      (node (ref "U$3") (pin "22") (pinfunction "PD5_22") (pintype "bidirectional"))
    )
    (net (code "14") (name "/RESET") (class "Default")
      (node (ref "GND") (pin "13") (pinfunction "~{RESET}_13") (pintype "bidirectional"))
      (node (ref "ICSP") (pin "5") (pinfunction "5_5") (pintype "bidirectional"))
      (node (ref "R4") (pin "1") (pinfunction "1_1") (pintype "passive"))
      (node (ref "U$3") (pin "13") (pinfunction "~{RESET}_13") (pintype "bidirectional"))
    )
    (net (code "15") (name "/RTC_BATT") (class "Default")
      (node (ref "BAT1") (pin "PWR@1") (pinfunction "+_PWR@1") (pintype "power_in"))
      (node (ref "U$14") (pin "6") (pinfunction "VBAT_6") (pintype "input"))
    )
    (net (code "16") (name "/RTC_INT") (class "Default")
      (node (ref "GND") (pin "20") (pinfunction "PD2(RX)_20") (pintype "bidirectional"))
      (node (ref "R2") (pin "2") (pinfunction "2_2") (pintype "passive"))
      (node (ref "U$14") (pin "3") (pinfunction "INT/SQW_3") (pintype "output"))
      (node (ref "U$3") (pin "20") (pinfunction "PD2(RX)_20") (pintype "bidirectional"))
    )
    (net (code "17") (name "/RXLED") (class "Default")
      (node (ref "GND") (pin "8") (pinfunction "PB0(SS)_8") (pintype "bidirectional"))
      (node (ref "U$3") (pin "8") (pinfunction "PB0(SS)_8") (pintype "bidirectional"))
    )
    (net (code "18") (name "/SCK") (class "Default")
      (node (ref "GND") (pin "9") (pinfunction "PB1(SCK)_9") (pintype "bidirectional"))
      (node (ref "ICSP") (pin "3") (pinfunction "3_3") (pintype "bidirectional"))
      (node (ref "J1") (pin "5") (pinfunction "SCLK_5") (pintype "bidirectional"))
      (node (ref "U$3") (pin "9") (pinfunction "PB1(SCK)_9") (pintype "bidirectional"))
      (node (ref "U$4") (pin "6") (pinfunction "CLK_6") (pintype "bidirectional"))
      (node (ref "X1") (pin "7") (pinfunction "1_7") (pintype "passive"))
    )
    (net (code "19") (name "/SCL") (class "Default")
      (node (ref "GND") (pin "18") (pinfunction "PD0(SCL)_18") (pintype "bidirectional"))
      (node (ref "IC1") (pin "8") (pinfunction "SCL_8") (pintype "input"))
      (node (ref "ICSP1") (pin "1") (pinfunction "1_1") (pintype "bidirectional"))
      (node (ref "R14") (pin "1") (pinfunction "1_1") (pintype "passive"))
      (node (ref "U$14") (pin "8") (pinfunction "SCL_8") (pintype "input"))
      (node (ref "U$3") (pin "18") (pinfunction "PD0(SCL)_18") (pintype "bidirectional"))
      (node (ref "U1") (pin "4") (pinfunction "4_4") (pintype "bidirectional"))
    )
    (net (code "20") (name "/SDA") (class "Default")
      (node (ref "GND") (pin "19") (pinfunction "PD1(SDA)_19") (pintype "bidirectional"))
      (node (ref "IC1") (pin "7") (pinfunction "SDA_7") (pintype "bidirectional"))
      (node (ref "ICSP1") (pin "2") (pinfunction "2_2") (pintype "bidirectional"))
      (node (ref "R13") (pin "1") (pinfunction "1_1") (pintype "passive"))
      (node (ref "U$14") (pin "7") (pinfunction "SDA_7") (pintype "bidirectional"))
      (node (ref "U$3") (pin "19") (pinfunction "PD1(SDA)_19") (pintype "bidirectional"))
      (node (ref "U1") (pin "5") (pinfunction "5_5") (pintype "bidirectional"))
    )
    (net (code "21") (name "/SD_CS") (class "Default")
      (node (ref "GND") (pin "31") (pinfunction "PC6_31") (pintype "bidirectional"))
      (node (ref "J1") (pin "2") (pinfunction "CS_2") (pintype "bidirectional"))
      (node (ref "TP7") (pin "P$1") (pinfunction "1_P$1") (pintype "bidirectional"))
      (node (ref "U$3") (pin "31") (pinfunction "PC6_31") (pintype "bidirectional"))
    )
    (net (code "22") (name "/SW_PWR") (class "Default")
      (node (ref "GND") (pin "12") (pinfunction "PB7_12") (pintype "bidirectional"))
      (node (ref "Q5") (pin "3") (pinfunction "D_3") (pintype "passive"))
      (node (ref "R18") (pin "1") (pinfunction "1_1") (pintype "passive"))
      (node (ref "TP9") (pin "P$1") (pinfunction "1_P$1") (pintype "bidirectional"))
      (node (ref "U$3") (pin "12") (pinfunction "PB7_12") (pintype "bidirectional"))
    )
    (net (code "23") (name "/TC1+") (class "Default")
      (node (ref "C10") (pin "1") (pinfunction "1_1") (pintype "passive"))
      (node (ref "C16") (pin "1") (pinfunction "1_1") (pintype "passive"))
      (node (ref "IC1") (pin "3") (pinfunction "CH2+_3") (pintype "input"))
      (node (ref "R39") (pin "1") (pinfunction "1_1") (pintype "passive"))
    )
    (net (code "24") (name "/TC1-") (class "Default")
      (node (ref "C10") (pin "2") (pinfunction "2_2") (pintype "passive"))
      (node (ref "C15") (pin "1") (pinfunction "1_1") (pintype "passive"))
      (node (ref "IC1") (pin "4") (pinfunction "CH2-_4") (pintype "input"))
      (node (ref "R41") (pin "2") (pinfunction "2_2") (pintype "passive"))
    )
    (net (code "25") (name "/TC2+") (class "Default")
      (node (ref "C11") (pin "1") (pinfunction "1_1") (pintype "passive"))
      (node (ref "C14") (pin "1") (pinfunction "1_1") (pintype "passive"))
      (node (ref "IC1") (pin "1") (pinfunction "CH1+_1") (pintype "input"))
      (node (ref "R40") (pin "1") (pinfunction "1_1") (pintype "passive"))
    )
    (net (code "26") (name "/TC2-") (class "Default")
      (node (ref "C11") (pin "2") (pinfunction "2_2") (pintype "passive"))
      (node (ref "C13") (pin "1") (pinfunction "1_1") (pintype "passive"))
      (node (ref "IC1") (pin "2") (pinfunction "CH1-_2") (pintype "input"))
      (node (ref "R42") (pin "2") (pinfunction "2_2") (pintype "passive"))
    )
    (net (code "27") (name "/TC3+") (class "Default")
      (node (ref "C17") (pin "2") (pinfunction "2_2") (pintype "passive"))
      (node (ref "C7") (pin "1") (pinfunction "1_1") (pintype "passive"))
      (node (ref "IC1") (pin "13") (pinfunction "CH4+_13") (pintype "input"))
      (node (ref "R35") (pin "1") (pinfunction "1_1") (pintype "passive"))
    )
    (net (code "28") (name "/TC3-") (class "Default")
      (node (ref "C24") (pin "2") (pinfunction "2_2") (pintype "passive"))
      (node (ref "C7") (pin "2") (pinfunction "2_2") (pintype "passive"))
      (node (ref "IC1") (pin "14") (pinfunction "CH4-_14") (pintype "input"))
      (node (ref "R36") (pin "2") (pinfunction "2_2") (pintype "passive"))
    )
    (net (code "29") (name "/TC4+") (class "Default")
      (node (ref "C25") (pin "2") (pinfunction "2_2") (pintype "passive"))
      (node (ref "C8") (pin "1") (pinfunction "1_1") (pintype "passive"))
      (node (ref "IC1") (pin "11") (pinfunction "CH3+_11") (pintype "input"))
      (node (ref "R37") (pin "1") (pinfunction "1_1") (pintype "passive"))
    )
    (net (code "30") (name "/TC4-") (class "Default")
      (node (ref "C37") (pin "2") (pinfunction "2_2") (pintype "passive"))
      (node (ref "C8") (pin "2") (pinfunction "2_2") (pintype "passive"))
      (node (ref "IC1") (pin "12") (pinfunction "CH3-_12") (pintype "input"))
      (node (ref "R38") (pin "2") (pinfunction "2_2") (pintype "passive"))
    )
    (net (code "31") (name "/VBAT") (class "Default")
      (node (ref "C9") (pin "1") (pinfunction "1_1") (pintype "passive"))
      (node (ref "Q1") (pin "3") (pinfunction "D_3") (pintype "passive"))
      (node (ref "Q2") (pin "2") (pinfunction "S_2") (pintype "passive"))
      (node (ref "R5") (pin "1") (pinfunction "1_1") (pintype "passive"))
      (node (ref "SJ1") (pin "1") (pinfunction "1_1") (pintype "passive"))
      (node (ref "TP14") (pin "P$1") (pinfunction "1_P$1") (pintype "bidirectional"))
      (node (ref "U3") (pin "3") (pinfunction "VBAT_3") (pintype "power_in"))
    )
    (net (code "32") (name "/VBAT_EN") (class "Default")
      (node (ref "GND") (pin "25") (pinfunction "PD4(ADC8)_25") (pintype "bidirectional"))
      (node (ref "Q3") (pin "1") (pinfunction "G_1") (pintype "passive"))
      (node (ref "R23") (pin "2") (pinfunction "2_2") (pintype "passive"))
      (node (ref "U$3") (pin "25") (pinfunction "PD4(ADC8)_25") (pintype "bidirectional"))
    )
    (net (code "33") (name "/VBAT_SENSE") (class "Default")
      (node (ref "C23") (pin "1") (pinfunction "1_1") (pintype "passive"))
      (node (ref "GND") (pin "26") (pinfunction "PD6(ADC9)_26") (pintype "bidirectional"))
      (node (ref "R20") (pin "1") (pinfunction "1_1") (pintype "passive"))
      (node (ref "R24") (pin "1") (pinfunction "1_1") (pintype "passive"))
      (node (ref "TP4") (pin "P$1") (pinfunction "1_P$1") (pintype "bidirectional"))
      (node (ref "U$3") (pin "26") (pinfunction "PD6(ADC9)_26") (pintype "bidirectional"))
    )
    (net (code "34") (name "/VBUS") (class "Default")
      (node (ref "C1") (pin "1") (pinfunction "1_1") (pintype "passive"))
      (node (ref "C12") (pin "1") (pinfunction "1_1") (pintype "passive"))
      (node (ref "C2") (pin "1") (pinfunction "1_1") (pintype "passive"))
      (node (ref "C28") (pin "1") (pinfunction "1_1") (pintype "passive"))
      (node (ref "D2") (pin "C") (pinfunction "C_C") (pintype "passive"))
      (node (ref "IC3") (pin "8") (pinfunction "VCC_8") (pintype "power_in"))
      (node (ref "JP1") (pin "1") (pinfunction "1_1") (pintype "passive"))
      (node (ref "Q1") (pin "2") (pinfunction "S_2") (pintype "passive"))
      (node (ref "R6") (pin "1") (pinfunction "1_1") (pintype "passive"))
      (node (ref "R7") (pin "1") (pinfunction "1_1") (pintype "passive"))
      (node (ref "TP12") (pin "P$1") (pinfunction "1_P$1") (pintype "bidirectional"))
      (node (ref "U4") (pin "1") (pinfunction "IN_1") (pintype "input"))
    )
    (net (code "35") (name "/VBUS_IN") (class "Default")
      (node (ref "C6") (pin "1") (pinfunction "1_1") (pintype "passive"))
      (node (ref "D2") (pin "A") (pinfunction "A_A") (pintype "passive"))
      (node (ref "GND") (pin "7") (pinfunction "VBUS_7") (pintype "bidirectional"))
      (node (ref "ICSP") (pin "2") (pinfunction "2_2") (pintype "bidirectional"))
      (node (ref "R25") (pin "2") (pinfunction "2_2") (pintype "passive"))
      (node (ref "TP11") (pin "P$1") (pinfunction "1_P$1") (pintype "bidirectional"))
      (node (ref "U$1") (pin "PIN$1") (pinfunction "VCC_PIN$1") (pintype "bidirectional"))
      (node (ref "U$3") (pin "7") (pinfunction "VBUS_7") (pintype "bidirectional"))
      (node (ref "U2") (pin "3") (pinfunction "VCC_3") (pintype "power_in"))
      (node (ref "U3") (pin "4") (pinfunction "VIN_4") (pintype "power_in"))
    )
    (net (code "36") (name "/XTAL1") (class "Default")
      (node (ref "GND") (pin "17") (pinfunction "XTAL1_17") (pintype "bidirectional"))
      (node (ref "U$3") (pin "17") (pinfunction "XTAL1_17") (pintype "bidirectional"))
      (node (ref "Y1") (pin "1") (pinfunction "1_1") (pintype "passive"))
    )
    (net (code "37") (name "/XTAL2") (class "Default")
      (node (ref "GND") (pin "16") (pinfunction "XTAL2_16") (pintype "bidirectional"))
      (node (ref "U$3") (pin "16") (pinfunction "XTAL2_16") (pintype "bidirectional"))
      (node (ref "Y1") (pin "3") (pinfunction "3_3") (pintype "passive"))
    )
    (net (code "38") (name "3.3V") (class "Default")
      (node (ref "C18") (pin "1") (pinfunction "1_1") (pintype "passive"))
      (node (ref "C19") (pin "1") (pinfunction "1_1") (pintype "passive"))
      (node (ref "C20") (pin "2") (pinfunction "2_2") (pintype "passive"))
      (node (ref "C21") (pin "2") (pinfunction "2_2") (pintype "passive"))
      (node (ref "C26") (pin "1") (pinfunction "1_1") (pintype "passive"))
      (node (ref "C27") (pin "1") (pinfunction "1_1") (pintype "passive"))
      (node (ref "C29") (pin "1") (pinfunction "1_1") (pintype "passive"))
      (node (ref "C30") (pin "1") (pinfunction "1_1") (pintype "passive"))
      (node (ref "C31") (pin "1") (pinfunction "1_1") (pintype "passive"))
      (node (ref "C32") (pin "1") (pinfunction "1_1") (pintype "passive"))
      (node (ref "C33") (pin "1") (pinfunction "1_1") (pintype "passive"))
      (node (ref "C34") (pin "1") (pinfunction "1_1") (pintype "passive"))
      (node (ref "C5") (pin "1") (pinfunction "1_1") (pintype "passive"))
      (node (ref "GND") (pin "14") (pinfunction "VCC_14") (pintype "bidirectional"))
      (node (ref "GND") (pin "24") (pinfunction "AVCC_24") (pintype "bidirectional"))
      (node (ref "GND") (pin "34") (pinfunction "VCC_34") (pintype "bidirectional"))
      (node (ref "GND") (pin "44") (pinfunction "AVCC_44") (pintype "bidirectional"))
      (node (ref "GND") (pin "6") (pinfunction "UCAP_6") (pintype "bidirectional"))
      (node (ref "IC1") (pin "6") (pinfunction "VDD_6") (pintype "power_in"))
      (node (ref "ICSP1") (pin "6") (pinfunction "6_6") (pintype "bidirectional"))
      (node (ref "J1") (pin "4") (pinfunction "VDD_4") (pintype "bidirectional"))
      (node (ref "Q5") (pin "2") (pinfunction "S_2") (pintype "passive"))
      (node (ref "R1") (pin "1") (pinfunction "1_1") (pintype "passive"))
      (node (ref "R11") (pin "1") (pinfunction "1_1") (pintype "passive"))
      (node (ref "R12") (pin "1") (pinfunction "1_1") (pintype "passive"))
      (node (ref "R13") (pin "2") (pinfunction "2_2") (pintype "passive"))
      (node (ref "R14") (pin "2") (pinfunction "2_2") (pintype "passive"))
      (node (ref "R15") (pin "1") (pinfunction "1_1") (pintype "passive"))
      (node (ref "R16") (pin "1") (pinfunction "1_1") (pintype "passive"))
      (node (ref "R2") (pin "1") (pinfunction "1_1") (pintype "passive"))
      (node (ref "R27") (pin "2") (pinfunction "2_2") (pintype "passive"))
      (node (ref "R28") (pin "2") (pinfunction "2_2") (pintype "passive"))
      (node (ref "R29") (pin "2") (pinfunction "2_2") (pintype "passive"))
      (node (ref "R30") (pin "2") (pinfunction "2_2") (pintype "passive"))
      (node (ref "R4") (pin "2") (pinfunction "2_2") (pintype "passive"))
      (node (ref "R8") (pin "1") (pinfunction "1_1") (pintype "passive"))
      (node (ref "TP13") (pin "P$1") (pinfunction "1_P$1") (pintype "bidirectional"))
      (node (ref "U$14") (pin "2") (pinfunction "VCC_2") (pintype "power_in"))
      (node (ref "U$3") (pin "14") (pinfunction "VCC_14") (pintype "bidirectional"))
      (node (ref "U$3") (pin "24") (pinfunction "AVCC_24") (pintype "bidirectional"))
      (node (ref "U$3") (pin "34") (pinfunction "VCC_34") (pintype "bidirectional"))
      (node (ref "U$3") (pin "44") (pinfunction "AVCC_44") (pintype "bidirectional"))
      (node (ref "U$3") (pin "6") (pinfunction "UCAP_6") (pintype "bidirectional"))
      (node (ref "U$4") (pin "3") (pinfunction "~{WP}_3") (pintype "bidirectional"))
      (node (ref "U$4") (pin "7") (pinfunction "~{HOLD}_7") (pintype "bidirectional"))
      (node (ref "U$4") (pin "8") (pinfunction "VCC_8") (pintype "bidirectional"))
      (node (ref "U1") (pin "1") (pinfunction "1_1") (pintype "bidirectional"))
      (node (ref "U4") (pin "5") (pinfunction "OUT_5") (pintype "passive"))
      (node (ref "X1") (pin "12") (pinfunction "1_12") (pintype "passive"))
      (node (ref "X1") (pin "5") (pinfunction "1_5") (pintype "passive"))
    )
    (net (code "39") (name "D+") (class "Default")
      (node (ref "GND") (pin "4") (pinfunction "D+_4") (pintype "bidirectional"))
      (node (ref "R9") (pin "2") (pinfunction "2_2") (pintype "passive"))
      (node (ref "U$3") (pin "4") (pinfunction "D+_4") (pintype "bidirectional"))
    )
    (net (code "40") (name "D-") (class "Default")
      (node (ref "GND") (pin "3") (pinfunction "D-_3") (pintype "bidirectional"))
      (node (ref "R10") (pin "2") (pinfunction "2_2") (pintype "passive"))
      (node (ref "U$3") (pin "3") (pinfunction "D-_3") (pintype "bidirectional"))
    )
    (net (code "41") (name "GND") (class "Default")
      (node (ref "BAT1") (pin "GND") (pinfunction "-_GND") (pintype "power_in"))
      (node (ref "C1") (pin "2") (pinfunction "2_2") (pintype "passive"))
      (node (ref "C12") (pin "2") (pinfunction "2_2") (pintype "passive"))
      (node (ref "C18") (pin "2") (pinfunction "2_2") (pintype "passive"))
      (node (ref "C19") (pin "2") (pinfunction "2_2") (pintype "passive"))
      (node (ref "C2") (pin "2") (pinfunction "2_2") (pintype "passive"))
      (node (ref "C20") (pin "1") (pinfunction "1_1") (pintype "passive"))
      (node (ref "C21") (pin "1") (pinfunction "1_1") (pintype "passive"))
      (node (ref "C22") (pin "2") (pinfunction "2_2") (pintype "passive"))
      (node (ref "C23") (pin "2") (pinfunction "2_2") (pintype "passive"))
      (node (ref "C26") (pin "2") (pinfunction "2_2") (pintype "passive"))
      (node (ref "C27") (pin "2") (pinfunction "2_2") (pintype "passive"))
      (node (ref "C28") (pin "2") (pinfunction "2_2") (pintype "passive"))
      (node (ref "C29") (pin "2") (pinfunction "2_2") (pintype "passive"))
      (node (ref "C3") (pin "2") (pinfunction "2_2") (pintype "passive"))
      (node (ref "C30") (pin "2") (pinfunction "2_2") (pintype "passive"))
      (node (ref "C32") (pin "2") (pinfunction "2_2") (pintype "passive"))
      (node (ref "C33") (pin "2") (pinfunction "2_2") (pintype "passive"))
      (node (ref "C34") (pin "2") (pinfunction "2_2") (pintype "passive"))
      (node (ref "C36") (pin "1") (pinfunction "1_1") (pintype "passive"))
      (node (ref "C4") (pin "2") (pinfunction "2_2") (pintype "passive"))
      (node (ref "C5") (pin "2") (pinfunction "2_2") (pintype "passive"))
      (node (ref "C6") (pin "2") (pinfunction "2_2") (pintype "passive"))
      (node (ref "C9") (pin "2") (pinfunction "2_2") (pintype "passive"))
      (node (ref "GND") (pin "15") (pinfunction "GND_15") (pintype "bidirectional"))
      (node (ref "GND") (pin "23") (pinfunction "GND_23") (pintype "bidirectional"))
      (node (ref "GND") (pin "33") (pinfunction "PE2/~{HWB}_33") (pintype "bidirectional"))
      (node (ref "GND") (pin "35") (pinfunction "GND_35") (pintype "bidirectional"))
      (node (ref "GND") (pin "43") (pinfunction "GND_43") (pintype "bidirectional"))
      (node (ref "GND") (pin "5") (pinfunction "UGND_5") (pintype "bidirectional"))
      (node (ref "GND") (pin "P$1") (pinfunction "GND_PAD_P$1") (pintype "bidirectional"))
      (node (ref "IC1") (pin "5") (pinfunction "GND_5") (pintype "power_in"))
      (node (ref "IC1") (pin "9") (pinfunction "A0_9") (pintype "input"))
      (node (ref "IC3") (pin "1") (pinfunction "CLK_1") (pintype "input"))
      (node (ref "IC3") (pin "2") (pinfunction "D_2") (pintype "input"))
      (node (ref "IC3") (pin "4") (pinfunction "GND_4") (pintype "power_in"))
      (node (ref "ICSP") (pin "6") (pinfunction "6_6") (pintype "bidirectional"))
      (node (ref "ICSP1") (pin "5") (pinfunction "5_5") (pintype "bidirectional"))
      (node (ref "J1") (pin "6") (pinfunction "VSS_6") (pintype "bidirectional"))
      (node (ref "J1") (pin "G1") (pinfunction "G1_G1") (pintype "bidirectional"))
      (node (ref "J1") (pin "G2") (pinfunction "G2_G2") (pintype "bidirectional"))
      (node (ref "J1") (pin "G3") (pinfunction "G3_G3") (pintype "bidirectional"))
      (node (ref "J1") (pin "G4") (pinfunction "G4_G4") (pintype "bidirectional"))
      (node (ref "Q3") (pin "2") (pinfunction "S_2") (pintype "passive"))
      (node (ref "Q4") (pin "2") (pinfunction "S_2") (pintype "passive"))
      (node (ref "R18") (pin "2") (pinfunction "2_2") (pintype "passive"))
      (node (ref "R22") (pin "2") (pinfunction "2_2") (pintype "passive"))
      (node (ref "R23") (pin "1") (pinfunction "1_1") (pintype "passive"))
      (node (ref "R24") (pin "2") (pinfunction "2_2") (pintype "passive"))
      (node (ref "R25") (pin "1") (pinfunction "1_1") (pintype "passive"))
      (node (ref "R3") (pin "2") (pinfunction "2_2") (pintype "passive"))
      (node (ref "S1") (pin "1") (pinfunction "1_1") (pintype "passive"))
      (node (ref "S2") (pin "1") (pinfunction "1_1") (pintype "passive"))
      (node (ref "S3") (pin "1") (pinfunction "1_1") (pintype "passive"))
      (node (ref "S4") (pin "1") (pinfunction "1_1") (pintype "passive"))
      (node (ref "S5") (pin "1") (pinfunction "1_1") (pintype "passive"))
      (node (ref "S6") (pin "3") (pinfunction "2_3") (pintype "passive"))
      (node (ref "SJ2") (pin "1") (pinfunction "1_1") (pintype "passive"))
      (node (ref "TP15") (pin "P$1") (pinfunction "1_P$1") (pintype "bidirectional"))
      (node (ref "U$1") (pin "PAD$1") (pinfunction "SHIELD_PAD$1") (pintype "bidirectional"))
      (node (ref "U$1") (pin "PAD$10") (pinfunction "SHIELD_PAD$10") (pintype "bidirectional"))
      (node (ref "U$1") (pin "PAD$2") (pinfunction "SHIELD_PAD$2") (pintype "bidirectional"))
      (node (ref "U$1") (pin "PAD$3") (pinfunction "SHIELD_PAD$3") (pintype "bidirectional"))
      (node (ref "U$1") (pin "PAD$4") (pinfunction "SHIELD_PAD$4") (pintype "bidirectional"))
      (node (ref "U$1") (pin "PAD$5") (pinfunction "SHIELD_PAD$5") (pintype "bidirectional"))
      (node (ref "U$1") (pin "PAD$6") (pinfunction "SHIELD_PAD$6") (pintype "bidirectional"))
      (node (ref "U$1") (pin "PAD$7") (pinfunction "SHIELD_PAD$7") (pintype "bidirectional"))
      (node (ref "U$1") (pin "PAD$8") (pinfunction "SHIELD_PAD$8") (pintype "bidirectional"))
      (node (ref "U$1") (pin "PAD$9") (pinfunction "SHIELD_PAD$9") (pintype "bidirectional"))
      (node (ref "U$1") (pin "PIN$5") (pinfunction "GND_PIN$5") (pintype "bidirectional"))
      (node (ref "U$14") (pin "5") (pinfunction "GND_5") (pintype "power_in"))
      (node (ref "U$2") (pin "P$3") (pinfunction "GND_P$3") (pintype "bidirectional"))
      (node (ref "U$2") (pin "P$4") (pinfunction "P$4_P$4") (pintype "bidirectional"))
      (node (ref "U$2") (pin "P$5") (pinfunction "P$5_P$5") (pintype "bidirectional"))
      (node (ref "U$3") (pin "15") (pinfunction "GND_15") (pintype "bidirectional"))
      (node (ref "U$3") (pin "23") (pinfunction "GND_23") (pintype "bidirectional"))
      (node (ref "U$3") (pin "33") (pinfunction "PE2/~{HWB}_33") (pintype "bidirectional"))
      (node (ref "U$3") (pin "35") (pinfunction "GND_35") (pintype "bidirectional"))
      (node (ref "U$3") (pin "43") (pinfunction "GND_43") (pintype "bidirectional"))
      (node (ref "U$3") (pin "5") (pinfunction "UGND_5") (pintype "bidirectional"))
      (node (ref "U$4") (pin "4") (pinfunction "GND_4") (pintype "bidirectional"))
      (node (ref "U2") (pin "1") (pinfunction "GND_1") (pintype "power_in"))
      (node (ref "U3") (pin "2") (pinfunction "VSS_2") (pintype "power_in"))
      (node (ref "U4") (pin "2") (pinfunction "GND_2") (pintype "input"))
      (node (ref "X1") (pin "4") (pinfunction "1_4") (pintype "passive"))
      (node (ref "Y1") (pin "2") (pinfunction "2_2") (pintype "passive"))
      (node (ref "Z1") (pin "1") (pinfunction "1_1") (pintype "passive"))
      (node (ref "Z2") (pin "1") (pinfunction "1_1") (pintype "passive"))
    )
    (net (code "42") (name "Net-(C36-Pad2)") (class "Default")
      (node (ref "C36") (pin "2") (pinfunction "2_2") (pintype "passive"))
      (node (ref "X1") (pin "1") (pinfunction "1_1") (pintype "passive"))
    )
    (net (code "43") (name "Net-(GND-AREF)") (class "Default")
      (node (ref "C3") (pin "1") (pinfunction "1_1") (pintype "passive"))
      (node (ref "GND") (pin "42") (pinfunction "AREF_42") (pintype "bidirectional"))
      (node (ref "U$3") (pin "42") (pinfunction "AREF_42") (pintype "bidirectional"))
    )
    (net (code "44") (name "Net-(GND-UVCC)") (class "Default")
      (node (ref "GND") (pin "2") (pinfunction "UVCC_2") (pintype "bidirectional"))
      (node (ref "U$3") (pin "2") (pinfunction "UVCC_2") (pintype "bidirectional"))
    )
    (net (code "45") (name "Net-(IC3-Q)") (class "Default")
      (node (ref "IC3") (pin "5") (pinfunction "Q_5") (pintype "output"))
      (node (ref "R21") (pin "1") (pinfunction "1_1") (pintype "passive"))
    )
    (net (code "46") (name "Net-(IC3-~{CLR})") (class "Default")
      (node (ref "IC3") (pin "6") (pinfunction "~{CLR}_6") (pintype "input"))
      (node (ref "Q4") (pin "3") (pinfunction "D_3") (pintype "passive"))
      (node (ref "R7") (pin "2") (pinfunction "2_2") (pintype "passive"))
    )
    (net (code "47") (name "Net-(IC3-~{SET})") (class "Default")
      (node (ref "IC3") (pin "7") (pinfunction "~{SET}_7") (pintype "input"))
      (node (ref "Q5") (pin "1") (pinfunction "G_1") (pintype "passive"))
      (node (ref "R6") (pin "2") (pinfunction "2_2") (pintype "passive"))
      (node (ref "S6") (pin "1") (pinfunction "1_1") (pintype "passive"))
    )
    (net (code "48") (name "Net-(Q1-G)") (class "Default")
      (node (ref "Q1") (pin "1") (pinfunction "G_1") (pintype "passive"))
      (node (ref "U2") (pin "2") (pinfunction "~{RST}_2") (pintype "bidirectional"))
    )
    (net (code "49") (name "Net-(Q2-D)") (class "Default")
      (node (ref "Q2") (pin "3") (pinfunction "D_3") (pintype "passive"))
      (node (ref "R20") (pin "2") (pinfunction "2_2") (pintype "passive"))
    )
    (net (code "50") (name "Net-(Q2-G)") (class "Default")
      (node (ref "Q2") (pin "1") (pinfunction "G_1") (pintype "passive"))
      (node (ref "Q3") (pin "3") (pinfunction "D_3") (pintype "passive"))
      (node (ref "R5") (pin "2") (pinfunction "2_2") (pintype "passive"))
    )
    (net (code "51") (name "Net-(U$1-D+)") (class "Default")
      (node (ref "R9") (pin "1") (pinfunction "1_1") (pintype "passive"))
      (node (ref "U$1") (pin "PIN$3") (pinfunction "D+_PIN$3") (pintype "bidirectional"))
      (node (ref "Z1") (pin "2") (pinfunction "2_2") (pintype "passive"))
    )
    (net (code "52") (name "Net-(U$1-D-)") (class "Default")
      (node (ref "R10") (pin "1") (pinfunction "1_1") (pintype "passive"))
      (node (ref "U$1") (pin "PIN$2") (pinfunction "D-_PIN$2") (pintype "bidirectional"))
      (node (ref "Z2") (pin "2") (pinfunction "2_2") (pintype "passive"))
    )
    (net (code "53") (name "Net-(U$2-VBAT)") (class "Default")
      (node (ref "SJ1") (pin "2") (pinfunction "2_2") (pintype "passive"))
      (node (ref "U$2") (pin "P$1") (pinfunction "VBAT_P$1") (pintype "bidirectional"))
    )
    (net (code "54") (name "Net-(U$7-1)") (class "Default")
      (node (ref "R27") (pin "1") (pinfunction "1_1") (pintype "passive"))
      (node (ref "R35") (pin "2") (pinfunction "2_2") (pintype "passive"))
      (node (ref "U$7") (pin "P$1") (pinfunction "1_P$1") (pintype "passive"))
    )
    (net (code "55") (name "Net-(U$8-1)") (class "Default")
      (node (ref "R31") (pin "2") (pinfunction "2_2") (pintype "passive"))
      (node (ref "R36") (pin "1") (pinfunction "1_1") (pintype "passive"))
      (node (ref "U$8") (pin "P$1") (pinfunction "1_P$1") (pintype "passive"))
    )
    (net (code "56") (name "Net-(U$9-1)") (class "Default")
      (node (ref "R28") (pin "1") (pinfunction "1_1") (pintype "passive"))
      (node (ref "R37") (pin "2") (pinfunction "2_2") (pintype "passive"))
      (node (ref "U$9") (pin "P$1") (pinfunction "1_P$1") (pintype "passive"))
    )
    (net (code "57") (name "Net-(U$15-1)") (class "Default")
      (node (ref "R32") (pin "2") (pinfunction "2_2") (pintype "passive"))
      (node (ref "R38") (pin "1") (pinfunction "1_1") (pintype "passive"))
      (node (ref "U$15") (pin "P$1") (pinfunction "1_P$1") (pintype "passive"))
    )
    (net (code "58") (name "Net-(U$16-1)") (class "Default")
      (node (ref "R29") (pin "1") (pinfunction "1_1") (pintype "passive"))
      (node (ref "R39") (pin "2") (pinfunction "2_2") (pintype "passive"))
      (node (ref "U$16") (pin "P$1") (pinfunction "1_P$1") (pintype "passive"))
    )
    (net (code "59") (name "Net-(U$17-1)") (class "Default")
      (node (ref "R33") (pin "2") (pinfunction "2_2") (pintype "passive"))
      (node (ref "R41") (pin "1") (pinfunction "1_1") (pintype "passive"))
      (node (ref "U$17") (pin "P$1") (pinfunction "1_P$1") (pintype "passive"))
    )
    (net (code "60") (name "Net-(U$18-1)") (class "Default")
      (node (ref "R30") (pin "1") (pinfunction "1_1") (pintype "passive"))
      (node (ref "R40") (pin "2") (pinfunction "2_2") (pintype "passive"))
      (node (ref "U$18") (pin "P$1") (pinfunction "1_P$1") (pintype "passive"))
    )
    (net (code "61") (name "Net-(U$19-1)") (class "Default")
      (node (ref "R34") (pin "2") (pinfunction "2_2") (pintype "passive"))
      (node (ref "R42") (pin "1") (pinfunction "1_1") (pintype "passive"))
      (node (ref "U$19") (pin "P$1") (pinfunction "1_P$1") (pintype "passive"))
    )
    (net (code "62") (name "Net-(U3-PROG)") (class "Default")
      (node (ref "R3") (pin "1") (pinfunction "1_1") (pintype "passive"))
      (node (ref "U3") (pin "5") (pinfunction "PROG_5") (pintype "input"))
    )
    (net (code "63") (name "Net-(U3-STAT)") (class "Default")
      (node (ref "R17") (pin "2") (pinfunction "2_2") (pintype "passive"))
      (node (ref "U3") (pin "1") (pinfunction "STAT_1") (pintype "output"))
    )
    (net (code "64") (name "Net-(U4-BP)") (class "Default")
      (node (ref "C4") (pin "1") (pinfunction "1_1") (pintype "passive"))
      (node (ref "U4") (pin "4") (pinfunction "BP_4") (pintype "input"))
    )
    (net (code "65") (name "Net-(X1C-1)") (class "Default")
      (node (ref "R19") (pin "1") (pinfunction "1_1") (pintype "passive"))
      (node (ref "X1") (pin "11") (pinfunction "1_11") (pintype "passive"))
    )
    (net (code "66") (name "Net-(X1E-1)") (class "Default")
      (node (ref "C35") (pin "2") (pinfunction "2_2") (pintype "passive"))
      (node (ref "X1") (pin "2") (pinfunction "1_2") (pintype "passive"))
    )
    (net (code "67") (name "Net-(X1F-1)") (class "Default")
      (node (ref "C35") (pin "1") (pinfunction "1_1") (pintype "passive"))
      (node (ref "X1") (pin "3") (pinfunction "1_3") (pintype "passive"))
    )
    (net (code "68") (name "SW_A") (class "Default")
      (node (ref "GND") (pin "1") (pinfunction "PE6_1") (pintype "bidirectional"))
      (node (ref "R8") (pin "2") (pinfunction "2_2") (pintype "passive"))
      (node (ref "S3") (pin "3") (pinfunction "2_3") (pintype "passive"))
      (node (ref "U$3") (pin "1") (pinfunction "PE6_1") (pintype "bidirectional"))
    )
    (net (code "69") (name "SW_B") (class "Default")
      (node (ref "GND") (pin "21") (pinfunction "PD3(TX)_21") (pintype "bidirectional"))
      (node (ref "R11") (pin "2") (pinfunction "2_2") (pintype "passive"))
      (node (ref "S2") (pin "3") (pinfunction "2_3") (pintype "passive"))
      (node (ref "U$3") (pin "21") (pinfunction "PD3(TX)_21") (pintype "bidirectional"))
    )
    (net (code "70") (name "SW_C") (class "Default")
      (node (ref "GND") (pin "28") (pinfunction "PB4(ADC11)_28") (pintype "bidirectional"))
      (node (ref "R12") (pin "2") (pinfunction "2_2") (pintype "passive"))
      (node (ref "S1") (pin "3") (pinfunction "2_3") (pintype "passive"))
      (node (ref "U$3") (pin "28") (pinfunction "PB4(ADC11)_28") (pintype "bidirectional"))
    )
    (net (code "71") (name "SW_D") (class "Default")
      (node (ref "GND") (pin "29") (pinfunction "PB5(ADC12)_29") (pintype "bidirectional"))
      (node (ref "R15") (pin "2") (pinfunction "2_2") (pintype "passive"))
      (node (ref "S4") (pin "3") (pinfunction "2_3") (pintype "passive"))
      (node (ref "U$3") (pin "29") (pinfunction "PB5(ADC12)_29") (pintype "bidirectional"))
    )
    (net (code "72") (name "SW_E") (class "Default")
      (node (ref "GND") (pin "30") (pinfunction "PB6(ADC13)_30") (pintype "bidirectional"))
      (node (ref "R16") (pin "2") (pinfunction "2_2") (pintype "passive"))
      (node (ref "S5") (pin "3") (pinfunction "2_3") (pintype "passive"))
      (node (ref "U$3") (pin "30") (pinfunction "PB6(ADC13)_30") (pintype "bidirectional"))
    )
    (net (code "73") (name "unconnected-(IC1-A1-Pad10)") (class "Default")
      (node (ref "IC1") (pin "10") (pinfunction "A1_10") (pintype "input"))
    )
    (net (code "74") (name "unconnected-(IC3-~{Q}-Pad3)") (class "Default")
      (node (ref "IC3") (pin "3") (pinfunction "~{Q}_3") (pintype "output"))
    )
    (net (code "75") (name "unconnected-(J1-CDN-Pad9)") (class "Default")
      (node (ref "J1") (pin "9") (pinfunction "CDN_9") (pintype "bidirectional"))
    )
    (net (code "76") (name "unconnected-(J1-DATA1-Pad8)") (class "Default")
      (node (ref "J1") (pin "8") (pinfunction "DATA1_8") (pintype "bidirectional"))
    )
    (net (code "77") (name "unconnected-(J1-DATA2-Pad1)") (class "Default")
      (node (ref "J1") (pin "1") (pinfunction "DATA2_1") (pintype "bidirectional"))
    )
    (net (code "78") (name "unconnected-(U$1-ID-PadPIN$4)") (class "Default")
      (node (ref "U$1") (pin "PIN$4") (pinfunction "ID_PIN$4") (pintype "bidirectional"))
    )
    (net (code "79") (name "unconnected-(U$2-BSI-PadP$2)") (class "Default")
      (node (ref "U$2") (pin "P$2") (pinfunction "BSI_P$2") (pintype "bidirectional"))
    )
    (net (code "80") (name "unconnected-(U$14-32KHZ-Pad1)") (class "Default")
      (node (ref "U$14") (pin "1") (pinfunction "32KHZ_1") (pintype "output"))
    )
    (net (code "81") (name "unconnected-(U$14-RST-Pad4)") (class "Default")
      (node (ref "U$14") (pin "4") (pinfunction "RST_4") (pintype "bidirectional"))
    )
    (net (code "82") (name "unconnected-(U1-Pad3)") (class "Default")
      (node (ref "U1") (pin "3") (pinfunction "3_3") (pintype "bidirectional"))
    )
  )
)
